# PennyMan_Ard_R3_Shield_v8.net
KiCad netlist of a schematic drawn in EAGLE
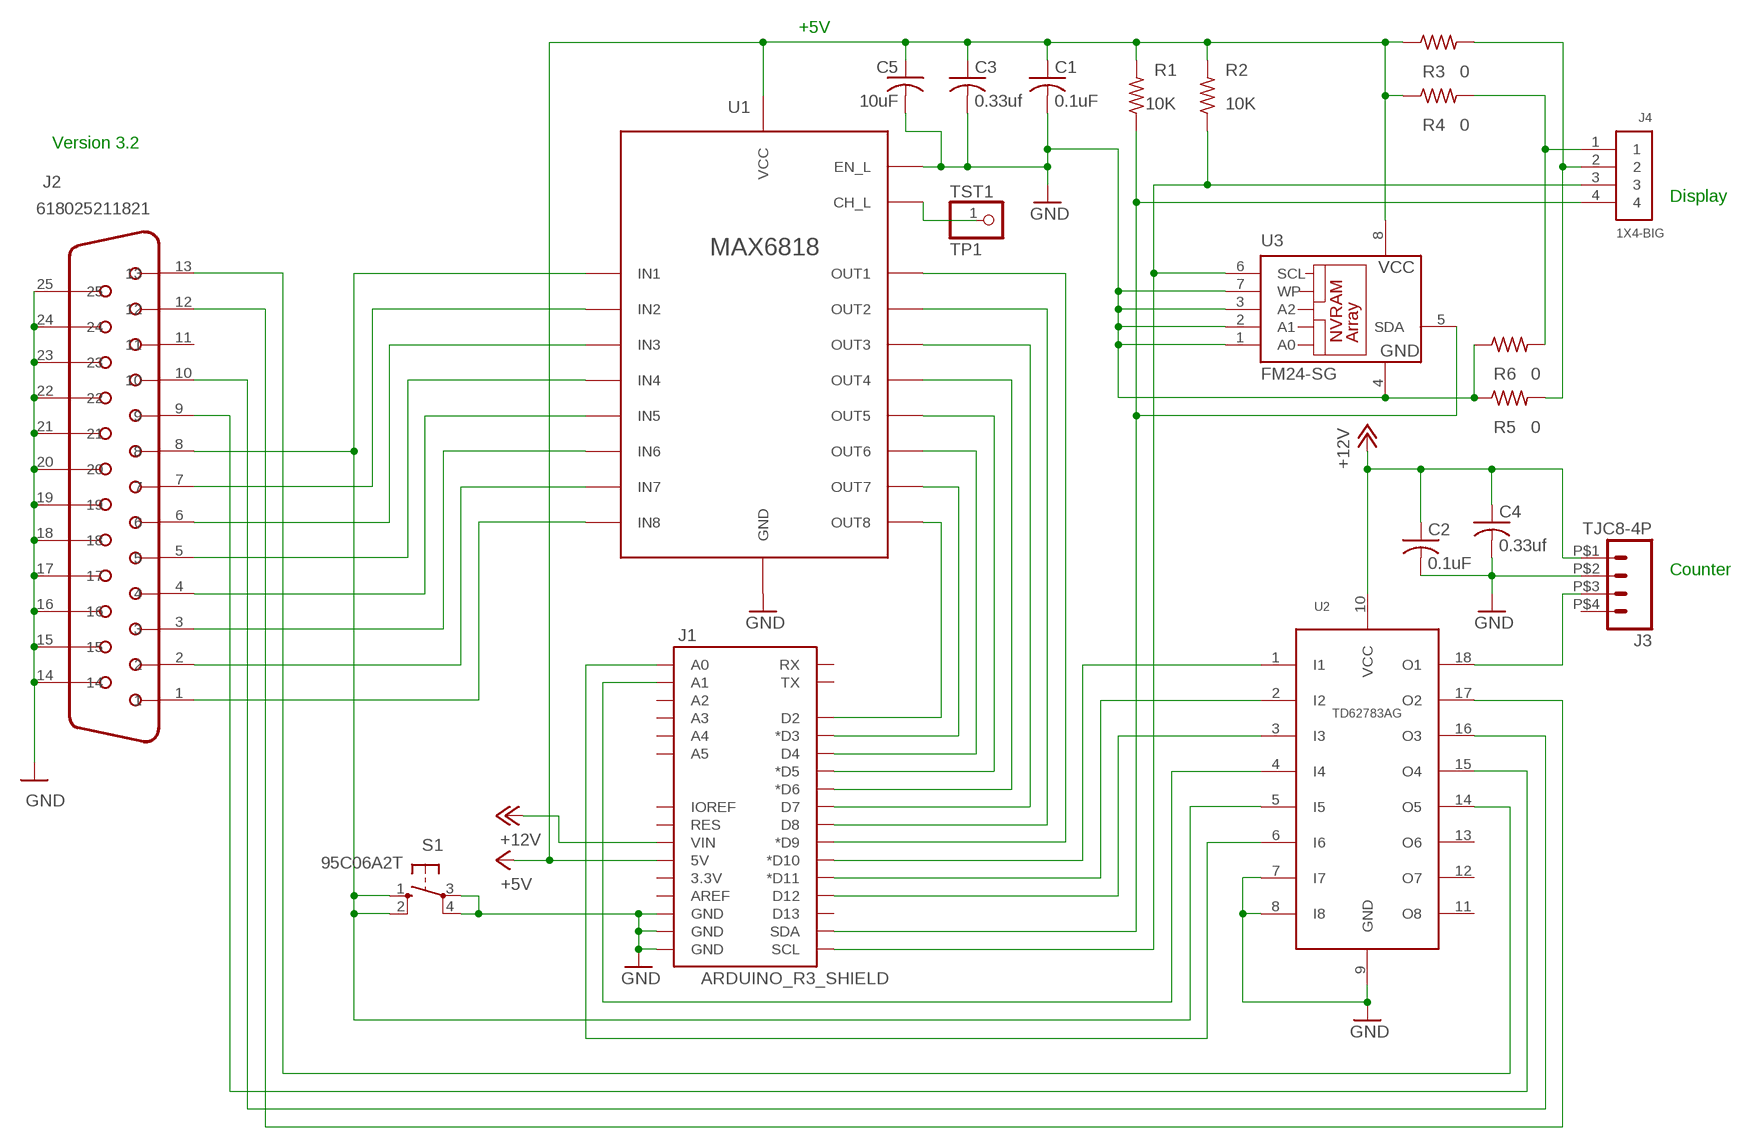
[diagram p0: schematic, sheet 1]

(export (version "E")
  (design (tool "Eeschema 10.0.6"))
  (components
    (comp (ref "C1")
      (value "0.1uF")
      (footprint "eagle-import:C0805")
      (libsource (lib "eagle-import") (part "C-USC0805"))
    )
    (comp (ref "C2")
      (value "0.1uF")
      (footprint "eagle-import:C0805")
      (libsource (lib "eagle-import") (part "C-USC0805"))
    )
    (comp (ref "C3")
      (value "0.33uf")
      (footprint "eagle-import:C1206")
      (libsource (lib "eagle-import") (part "C-USC1206"))
    )
    (comp (ref "C4")
      (value "0.33uf")
      (footprint "eagle-import:C1206")
      (libsource (lib "eagle-import") (part "C-USC1206"))
    )
    (comp (ref "C5")
      (value "10uF")
      (footprint "eagle-import:C1812")
      (libsource (lib "eagle-import") (part "C-USC1812"))
    )
    (comp (ref "J1")
      (value "ARDUINO_R3_SHIELD")
      (footprint "eagle-import:UNO_R3_SHIELD")
      (libsource (lib "eagle-import") (part "ARDUINO_R3_SHIELD"))
    )
    (comp (ref "J2")
      (value "618025211821")
      (footprint "eagle-import:618025211821")
      (libsource (lib "eagle-import") (part "618025211821"))
    )
    (comp (ref "J3")
      (value "TJC8-4P")
      (footprint "eagle-import:TJC8-4P")
      (libsource (lib "eagle-import") (part "TJC8-4P"))
    )
    (comp (ref "J4")
      (value "1X4-BIG")
      (footprint "eagle-import:1X04-BIG")
      (libsource (lib "eagle-import") (part "1X4-BIG"))
    )
    (comp (ref "R1")
      (value "10K")
      (footprint "eagle-import:R0805")
      (libsource (lib "eagle-import") (part "R-US_R0805"))
    )
    (comp (ref "R2")
      (value "10K")
      (footprint "eagle-import:R0805")
      (libsource (lib "eagle-import") (part "R-US_R0805"))
    )
    (comp (ref "R3")
      (value "0")
      (footprint "eagle-import:R0805")
      (libsource (lib "eagle-import") (part "R-US_R0805"))
    )
    (comp (ref "R4")
      (value "0")
      (footprint "eagle-import:R0805")
      (libsource (lib "eagle-import") (part "R-US_R0805"))
    )
    (comp (ref "R5")
      (value "0")
      (footprint "eagle-import:R0805")
      (libsource (lib "eagle-import") (part "R-US_R0805"))
    )
    (comp (ref "R6")
      (value "0")
      (footprint "eagle-import:R0805")
      (libsource (lib "eagle-import") (part "R-US_R0805"))
    )
    (comp (ref "S1")
      (value "95C06A2T")
      (footprint "eagle-import:B3F-10XX")
      (libsource (lib "eagle-import") (part "10-XX"))
    )
    (comp (ref "TST1")
      (value "TP1")
      (footprint "eagle-import:1X01")
      (libsource (lib "eagle-import") (part "PINHD-1X1"))
    )
    (comp (ref "U1")
      (value "MAX6818")
      (footprint "eagle-import:SSOP20")
      (libsource (lib "eagle-import") (part "MAX6818"))
    )
    (comp (ref "U2")
      (value "TD62783AG")
      (footprint "eagle-import:SOP18")
      (libsource (lib "eagle-import") (part "TD62783AG"))
    )
    (comp (ref "U3")
      (value "FM24-SG")
      (footprint "eagle-import:SO8")
      (libsource (lib "eagle-import") (part "FM24-SG"))
    )
  )
  (nets
    (net (code "1") (name "+5V") (class "Default")
      (node (ref "C1") (pin "1") (pinfunction "1_1") (pintype "passive"))
      (node (ref "C3") (pin "1") (pinfunction "1_1") (pintype "passive"))
      (node (ref "C5") (pin "1") (pinfunction "1_1") (pintype "passive"))
      (node (ref "J1") (pin "5V") (pinfunction "5V_5V") (pintype "bidirectional"))
      (node (ref "R1") (pin "2") (pinfunction "2_2") (pintype "passive"))
      (node (ref "R2") (pin "2") (pinfunction "2_2") (pintype "passive"))
      (node (ref "R3") (pin "1") (pinfunction "1_1") (pintype "passive"))
      (node (ref "R4") (pin "1") (pinfunction "1_1") (pintype "passive"))
      (node (ref "U1") (pin "VCC") (pinfunction "VCC_VCC") (pintype "bidirectional"))
      (node (ref "U3") (pin "8") (pinfunction "VCC_8") (pintype "power_in"))
    )
    (net (code "2") (name "+12V") (class "Default")
      (node (ref "C2") (pin "1") (pinfunction "1_1") (pintype "passive"))
      (node (ref "C4") (pin "1") (pinfunction "1_1") (pintype "passive"))
      (node (ref "J1") (pin "VIN") (pinfunction "VIN_VIN") (pintype "bidirectional"))
      (node (ref "J3") (pin "P$1") (pinfunction "1_P$1") (pintype "passive"))
      (node (ref "U2") (pin "10") (pinfunction "VCC_10") (pintype "bidirectional"))
    )
    (net (code "3") (name "GND") (class "Default")
      (node (ref "C1") (pin "2") (pinfunction "2_2") (pintype "passive"))
      (node (ref "C2") (pin "2") (pinfunction "2_2") (pintype "passive"))
      (node (ref "C3") (pin "2") (pinfunction "2_2") (pintype "passive"))
      (node (ref "C4") (pin "2") (pinfunction "2_2") (pintype "passive"))
      (node (ref "C5") (pin "2") (pinfunction "2_2") (pintype "passive"))
      (node (ref "J1") (pin "GND@0") (pinfunction "GND_GND@0") (pintype "bidirectional"))
      (node (ref "J1") (pin "GND@1") (pinfunction "GND_GND@1") (pintype "bidirectional"))
      (node (ref "J1") (pin "GND@2") (pinfunction "GND_GND@2") (pintype "bidirectional"))
      (node (ref "J2") (pin "14") (pinfunction "14_14") (pintype "bidirectional"))
      (node (ref "J2") (pin "15") (pinfunction "15_15") (pintype "bidirectional"))
      (node (ref "J2") (pin "16") (pinfunction "16_16") (pintype "bidirectional"))
      (node (ref "J2") (pin "17") (pinfunction "17_17") (pintype "bidirectional"))
      (node (ref "J2") (pin "18") (pinfunction "18_18") (pintype "bidirectional"))
      (node (ref "J2") (pin "19") (pinfunction "19_19") (pintype "bidirectional"))
      (node (ref "J2") (pin "20") (pinfunction "20_20") (pintype "bidirectional"))
      (node (ref "J2") (pin "21") (pinfunction "21_21") (pintype "bidirectional"))
      (node (ref "J2") (pin "22") (pinfunction "22_22") (pintype "bidirectional"))
      (node (ref "J2") (pin "23") (pinfunction "23_23") (pintype "bidirectional"))
      (node (ref "J2") (pin "24") (pinfunction "24_24") (pintype "bidirectional"))
      (node (ref "J2") (pin "25") (pinfunction "25_25") (pintype "bidirectional"))
      (node (ref "J3") (pin "P$2") (pinfunction "2_P$2") (pintype "passive"))
      (node (ref "R5") (pin "1") (pinfunction "1_1") (pintype "passive"))
      (node (ref "R6") (pin "1") (pinfunction "1_1") (pintype "passive"))
      (node (ref "S1") (pin "3") (pinfunction "P_3") (pintype "passive"))
      (node (ref "S1") (pin "4") (pinfunction "P1_4") (pintype "passive"))
      (node (ref "U1") (pin "EN_L") (pinfunction "EN_L_EN_L") (pintype "bidirectional"))
      (node (ref "U1") (pin "GND") (pinfunction "GND_GND") (pintype "bidirectional"))
      (node (ref "U2") (pin "7") (pinfunction "I7_7") (pintype "bidirectional"))
      (node (ref "U2") (pin "8") (pinfunction "I8_8") (pintype "bidirectional"))
      (node (ref "U2") (pin "9") (pinfunction "GND_9") (pintype "bidirectional"))
      (node (ref "U3") (pin "1") (pinfunction "A0_1") (pintype "passive"))
      (node (ref "U3") (pin "2") (pinfunction "A1_2") (pintype "passive"))
      (node (ref "U3") (pin "3") (pinfunction "A2_3") (pintype "passive"))
      (node (ref "U3") (pin "4") (pinfunction "GND_4") (pintype "power_in"))
      (node (ref "U3") (pin "7") (pinfunction "WP_7") (pintype "input"))
    )
    (net (code "4") (name "Net-(J1-*D3)") (class "Default")
      (node (ref "J1") (pin "D3") (pinfunction "*D3_D3") (pintype "bidirectional"))
      (node (ref "U1") (pin "OUT7") (pinfunction "OUT7_OUT7") (pintype "bidirectional"))
    )
    (net (code "5") (name "Net-(J1-*D5)") (class "Default")
      (node (ref "J1") (pin "D5") (pinfunction "*D5_D5") (pintype "bidirectional"))
      (node (ref "U1") (pin "OUT5") (pinfunction "OUT5_OUT5") (pintype "bidirectional"))
    )
    (net (code "6") (name "Net-(J1-*D6)") (class "Default")
      (node (ref "J1") (pin "D6") (pinfunction "*D6_D6") (pintype "bidirectional"))
      (node (ref "U1") (pin "OUT4") (pinfunction "OUT4_OUT4") (pintype "bidirectional"))
    )
    (net (code "7") (name "Net-(J1-*D9)") (class "Default")
      (node (ref "J1") (pin "D9") (pinfunction "*D9_D9") (pintype "bidirectional"))
      (node (ref "U1") (pin "OUT1") (pinfunction "OUT1_OUT1") (pintype "bidirectional"))
    )
    (net (code "8") (name "Net-(J1-*D10)") (class "Default")
      (node (ref "J1") (pin "D10") (pinfunction "*D10_D10") (pintype "bidirectional"))
      (node (ref "U2") (pin "1") (pinfunction "I1_1") (pintype "bidirectional"))
    )
    (net (code "9") (name "Net-(J1-*D11)") (class "Default")
      (node (ref "J1") (pin "D11") (pinfunction "*D11_D11") (pintype "bidirectional"))
      (node (ref "U2") (pin "2") (pinfunction "I2_2") (pintype "bidirectional"))
    )
    (net (code "10") (name "Net-(J1-PadD2)") (class "Default")
      (node (ref "J1") (pin "D2") (pinfunction "D2_D2") (pintype "bidirectional"))
      (node (ref "U1") (pin "OUT8") (pinfunction "OUT8_OUT8") (pintype "bidirectional"))
    )
    (net (code "11") (name "Net-(J1-PadD4)") (class "Default")
      (node (ref "J1") (pin "D4") (pinfunction "D4_D4") (pintype "bidirectional"))
      (node (ref "U1") (pin "OUT6") (pinfunction "OUT6_OUT6") (pintype "bidirectional"))
    )
    (net (code "12") (name "Net-(J1-PadD7)") (class "Default")
      (node (ref "J1") (pin "D7") (pinfunction "D7_D7") (pintype "bidirectional"))
      (node (ref "U1") (pin "OUT3") (pinfunction "OUT3_OUT3") (pintype "bidirectional"))
    )
    (net (code "13") (name "Net-(J1-PadD8)") (class "Default")
      (node (ref "J1") (pin "D8") (pinfunction "D8_D8") (pintype "bidirectional"))
      (node (ref "U1") (pin "OUT2") (pinfunction "OUT2_OUT2") (pintype "bidirectional"))
    )
    (net (code "14") (name "Net-(J2-Pad1)") (class "Default")
      (node (ref "J2") (pin "1") (pinfunction "1_1") (pintype "bidirectional"))
      (node (ref "U1") (pin "IN8") (pinfunction "IN8_IN8") (pintype "bidirectional"))
    )
    (net (code "15") (name "Net-(J2-Pad2)") (class "Default")
      (node (ref "J2") (pin "2") (pinfunction "2_2") (pintype "bidirectional"))
      (node (ref "U1") (pin "IN7") (pinfunction "IN7_IN7") (pintype "bidirectional"))
    )
    (net (code "16") (name "Net-(J2-Pad3)") (class "Default")
      (node (ref "J2") (pin "3") (pinfunction "3_3") (pintype "bidirectional"))
      (node (ref "U1") (pin "IN6") (pinfunction "IN6_IN6") (pintype "bidirectional"))
    )
    (net (code "17") (name "Net-(J2-Pad4)") (class "Default")
      (node (ref "J2") (pin "4") (pinfunction "4_4") (pintype "bidirectional"))
      (node (ref "U1") (pin "IN5") (pinfunction "IN5_IN5") (pintype "bidirectional"))
    )
    (net (code "18") (name "Net-(J2-Pad5)") (class "Default")
      (node (ref "J2") (pin "5") (pinfunction "5_5") (pintype "bidirectional"))
      (node (ref "U1") (pin "IN4") (pinfunction "IN4_IN4") (pintype "bidirectional"))
    )
    (net (code "19") (name "Net-(J2-Pad6)") (class "Default")
      (node (ref "J2") (pin "6") (pinfunction "6_6") (pintype "bidirectional"))
      (node (ref "U1") (pin "IN3") (pinfunction "IN3_IN3") (pintype "bidirectional"))
    )
    (net (code "20") (name "Net-(J2-Pad7)") (class "Default")
      (node (ref "J2") (pin "7") (pinfunction "7_7") (pintype "bidirectional"))
      (node (ref "U1") (pin "IN2") (pinfunction "IN2_IN2") (pintype "bidirectional"))
    )
    (net (code "21") (name "Net-(J3-3)") (class "Default")
      (node (ref "J3") (pin "P$3") (pinfunction "3_P$3") (pintype "passive"))
      (node (ref "U2") (pin "18") (pinfunction "O1_18") (pintype "bidirectional"))
    )
    (net (code "22") (name "Net-(J4-Pad1)") (class "Default")
      (node (ref "J4") (pin "1") (pinfunction "1_1") (pintype "bidirectional"))
      (node (ref "R4") (pin "2") (pinfunction "2_2") (pintype "passive"))
      (node (ref "R6") (pin "2") (pinfunction "2_2") (pintype "passive"))
    )
    (net (code "23") (name "Net-(J4-Pad2)") (class "Default")
      (node (ref "J4") (pin "2") (pinfunction "2_2") (pintype "bidirectional"))
      (node (ref "R3") (pin "2") (pinfunction "2_2") (pintype "passive"))
      (node (ref "R5") (pin "2") (pinfunction "2_2") (pintype "passive"))
    )
    (net (code "24") (name "Net-(S1-S)") (class "Default")
      (node (ref "J2") (pin "8") (pinfunction "8_8") (pintype "bidirectional"))
      (node (ref "S1") (pin "1") (pinfunction "S_1") (pintype "passive"))
      (node (ref "S1") (pin "2") (pinfunction "S1_2") (pintype "passive"))
      (node (ref "U1") (pin "IN1") (pinfunction "IN1_IN1") (pintype "bidirectional"))
      (node (ref "U2") (pin "5") (pinfunction "I5_5") (pintype "bidirectional"))
    )
    (net (code "25") (name "Net-(TST1-Pad1)") (class "Default")
      (node (ref "TST1") (pin "1") (pinfunction "1_1") (pintype "passive"))
      (node (ref "U1") (pin "CH_L") (pinfunction "CH_L_CH_L") (pintype "bidirectional"))
    )
    (net (code "26") (name "Net-(U2-I3)") (class "Default")
      (node (ref "J1") (pin "D12") (pinfunction "D12_D12") (pintype "bidirectional"))
      (node (ref "U2") (pin "3") (pinfunction "I3_3") (pintype "bidirectional"))
    )
    (net (code "27") (name "Net-(U2-I4)") (class "Default")
      (node (ref "J1") (pin "A1") (pinfunction "A1_A1") (pintype "bidirectional"))
      (node (ref "U2") (pin "4") (pinfunction "I4_4") (pintype "bidirectional"))
    )
    (net (code "28") (name "Net-(U2-I6)") (class "Default")
      (node (ref "J1") (pin "A0") (pinfunction "A0_A0") (pintype "bidirectional"))
      (node (ref "U2") (pin "6") (pinfunction "I6_6") (pintype "bidirectional"))
    )
    (net (code "29") (name "Net-(U2-O2)") (class "Default")
      (node (ref "J2") (pin "12") (pinfunction "12_12") (pintype "bidirectional"))
      (node (ref "U2") (pin "17") (pinfunction "O2_17") (pintype "bidirectional"))
    )
    (net (code "30") (name "Net-(U2-O3)") (class "Default")
      (node (ref "J2") (pin "10") (pinfunction "10_10") (pintype "bidirectional"))
      (node (ref "U2") (pin "16") (pinfunction "O3_16") (pintype "bidirectional"))
    )
    (net (code "31") (name "Net-(U2-O4)") (class "Default")
      (node (ref "J2") (pin "9") (pinfunction "9_9") (pintype "bidirectional"))
      (node (ref "U2") (pin "15") (pinfunction "O4_15") (pintype "bidirectional"))
    )
    (net (code "32") (name "Net-(U2-O5)") (class "Default")
      (node (ref "J2") (pin "13") (pinfunction "13_13") (pintype "bidirectional"))
      (node (ref "U2") (pin "14") (pinfunction "O5_14") (pintype "bidirectional"))
    )
    (net (code "33") (name "Net-(U3-SCL)") (class "Default")
      (node (ref "J1") (pin "SCL") (pinfunction "SCL_SCL") (pintype "bidirectional"))
      (node (ref "J4") (pin "3") (pinfunction "3_3") (pintype "bidirectional"))
      (node (ref "R2") (pin "1") (pinfunction "1_1") (pintype "passive"))
      (node (ref "U3") (pin "6") (pinfunction "SCL_6") (pintype "input"))
    )
    (net (code "34") (name "Net-(U3-SDA)") (class "Default")
      (node (ref "J1") (pin "SDA") (pinfunction "SDA_SDA") (pintype "bidirectional"))
      (node (ref "J4") (pin "4") (pinfunction "4_4") (pintype "bidirectional"))
      (node (ref "R1") (pin "1") (pinfunction "1_1") (pintype "passive"))
      (node (ref "U3") (pin "5") (pinfunction "SDA_5") (pintype "bidirectional"))
    )
    (net (code "35") (name "unconnected-(J1-Pad3.3V)") (class "Default")
      (node (ref "J1") (pin "3.3V") (pinfunction "3.3V_3.3V") (pintype "bidirectional"))
    )
    (net (code "36") (name "unconnected-(J1-PadA2)") (class "Default")
      (node (ref "J1") (pin "A2") (pinfunction "A2_A2") (pintype "bidirectional"))
    )
    (net (code "37") (name "unconnected-(J1-PadA3)") (class "Default")
      (node (ref "J1") (pin "A3") (pinfunction "A3_A3") (pintype "bidirectional"))
    )
    (net (code "38") (name "unconnected-(J1-PadA4)") (class "Default")
      (node (ref "J1") (pin "A4") (pinfunction "A4_A4") (pintype "bidirectional"))
    )
    (net (code "39") (name "unconnected-(J1-PadA5)") (class "Default")
      (node (ref "J1") (pin "A5") (pinfunction "A5_A5") (pintype "bidirectional"))
    )
    (net (code "40") (name "unconnected-(J1-PadAREF)") (class "Default")
      (node (ref "J1") (pin "AREF") (pinfunction "AREF_AREF") (pintype "bidirectional"))
    )
    (net (code "41") (name "unconnected-(J1-PadD13)") (class "Default")
      (node (ref "J1") (pin "D13") (pinfunction "D13_D13") (pintype "bidirectional"))
    )
    (net (code "42") (name "unconnected-(J1-PadIOREF)") (class "Default")
      (node (ref "J1") (pin "IOREF") (pinfunction "IOREF_IOREF") (pintype "bidirectional"))
    )
    (net (code "43") (name "unconnected-(J1-PadRES)") (class "Default")
      (node (ref "J1") (pin "RES") (pinfunction "RES_RES") (pintype "bidirectional"))
    )
    (net (code "44") (name "unconnected-(J1-PadRX)") (class "Default")
      (node (ref "J1") (pin "RX") (pinfunction "RX_RX") (pintype "bidirectional"))
    )
    (net (code "45") (name "unconnected-(J1-PadTX)") (class "Default")
      (node (ref "J1") (pin "TX") (pinfunction "TX_TX") (pintype "bidirectional"))
    )
    (net (code "46") (name "unconnected-(J2-Pad11)") (class "Default")
      (node (ref "J2") (pin "11") (pinfunction "11_11") (pintype "bidirectional"))
    )
    (net (code "47") (name "unconnected-(J3-4-PadP$4)") (class "Default")
      (node (ref "J3") (pin "P$4") (pinfunction "4_P$4") (pintype "passive"))
    )
    (net (code "48") (name "unconnected-(U2-O6-Pad13)") (class "Default")
      (node (ref "U2") (pin "13") (pinfunction "O6_13") (pintype "bidirectional"))
    )
    (net (code "49") (name "unconnected-(U2-O7-Pad12)") (class "Default")
      (node (ref "U2") (pin "12") (pinfunction "O7_12") (pintype "bidirectional"))
    )
    (net (code "50") (name "unconnected-(U2-O8-Pad11)") (class "Default")
      (node (ref "U2") (pin "11") (pinfunction "O8_11") (pintype "bidirectional"))
    )
  )
)
